# 100Hz.net
KiCad netlist of a schematic drawn in Altium Designer
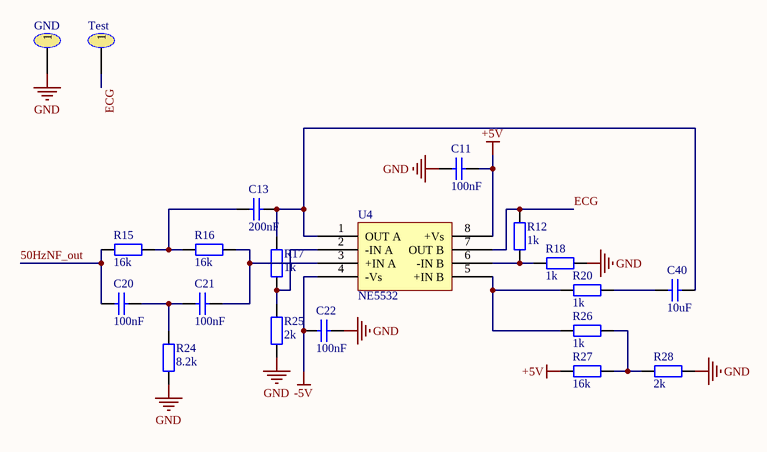
[diagram p0: 100Hz陷波&电平移位&放大.SchDoc]

(export (version "E")
  (design (tool "Eeschema 10.0.6"))
  (components
    (comp (ref "C11")
      (value "100nF")
      (footprint "LC-0805_C")
      (description "100nF��0805��50V,+/-10%")
      (libsource (lib "ECG") (part "Cap"))
    )
    (comp (ref "C13")
      (value "200nF")
      (footprint "LC-0805_C")
      (description "100nF��0805��50V,+/-10%")
      (libsource (lib "ECG") (part "Cap"))
    )
    (comp (ref "C20")
      (value "100nF")
      (footprint "LC-0805_C")
      (description "100nF��0805��50V,+/-10%")
      (libsource (lib "ECG") (part "Cap"))
    )
    (comp (ref "C21")
      (value "100nF")
      (footprint "LC-0805_C")
      (description "100nF��0805��50V,+/-10%")
      (libsource (lib "ECG") (part "Cap"))
    )
    (comp (ref "C22")
      (value "100nF")
      (footprint "LC-0805_C")
      (description "100nF��0805��50V,+/-10%")
      (libsource (lib "ECG") (part "Cap"))
    )
    (comp (ref "C40")
      (value "10uF")
      (footprint "LC-0805_C")
      (description "100nF��0805��50V,+/-10%")
      (libsource (lib "ECG") (part "Cap"))
    )
    (comp (ref "GND")
      (value "���Ժ���")
      (footprint "PAD")
      (description "��������")
      (libsource (lib "ECG") (part "TestPoint"))
    )
    (comp (ref "R12")
      (value "1k")
      (footprint "LC-0805_R")
      (description "10k��,0805,��5%")
      (libsource (lib "ECG") (part "R"))
    )
    (comp (ref "R15")
      (value "16k")
      (footprint "LC-0805_R")
      (description "10k��,0805,��5%")
      (libsource (lib "ECG") (part "R"))
    )
    (comp (ref "R16")
      (value "16k")
      (footprint "LC-0805_R")
      (description "10k��,0805,��5%")
      (libsource (lib "ECG") (part "R"))
    )
    (comp (ref "R17")
      (value "1k")
      (footprint "LC-0805_R")
      (description "10k��,0805,��5%")
      (libsource (lib "ECG") (part "R"))
    )
    (comp (ref "R18")
      (value "1k")
      (footprint "LC-0805_R")
      (description "10k��,0805,��5%")
      (libsource (lib "ECG") (part "R"))
    )
    (comp (ref "R20")
      (value "1k")
      (footprint "LC-0805_R")
      (description "10k��,0805,��5%")
      (libsource (lib "ECG") (part "R"))
    )
    (comp (ref "R24")
      (value "8.2k")
      (footprint "LC-0805_R")
      (description "10k��,0805,��5%")
      (libsource (lib "ECG") (part "R"))
    )
    (comp (ref "R25")
      (value "2k")
      (footprint "LC-0805_R")
      (description "10k��,0805,��5%")
      (libsource (lib "ECG") (part "R"))
    )
    (comp (ref "R26")
      (value "1k")
      (footprint "LC-0805_R")
      (description "10k��,0805,��5%")
      (libsource (lib "ECG") (part "R"))
    )
    (comp (ref "R27")
      (value "16k")
      (footprint "LC-0805_R")
      (description "10k��,0805,��5%")
      (libsource (lib "ECG") (part "R"))
    )
    (comp (ref "R28")
      (value "2k")
      (footprint "LC-0805_R")
      (description "10k��,0805,��5%")
      (libsource (lib "ECG") (part "R"))
    )
    (comp (ref "Test")
      (value "���Ժ���")
      (footprint "PAD")
      (description "��������")
      (libsource (lib "ECG") (part "TestPoint"))
    )
    (comp (ref "U4")
      (value "NE5532")
      (footprint "DIP-8")
      (description "NE5532��SO-8")
      (libsource (lib "ECG") (part "NE5532"))
    )
  )
  (nets
    (net (code "1") (name "+5V") (class "Default")
      (node (ref "C11") (pin "1") (pinfunction "1_1") (pintype "passive"))
      (node (ref "R27") (pin "2") (pintype "passive"))
      (node (ref "U4") (pin "8") (pinfunction "+Vs_8") (pintype "passive"))
    )
    (net (code "2") (name "-5V") (class "Default")
      (node (ref "C22") (pin "2") (pinfunction "2_2") (pintype "passive"))
      (node (ref "U4") (pin "4") (pinfunction "-Vs_4") (pintype "passive"))
    )
    (net (code "3") (name "/50HzNF_out") (class "Default")
      (node (ref "C20") (pin "2") (pinfunction "2_2") (pintype "passive"))
      (node (ref "R15") (pin "1") (pintype "passive"))
    )
    (net (code "4") (name "/ECG") (class "Default")
      (node (ref "R12") (pin "2") (pintype "passive"))
      (node (ref "Test") (pin "1") (pinfunction "1_1") (pintype "passive"))
      (node (ref "U4") (pin "7") (pinfunction "OUT_B_7") (pintype "passive"))
    )
    (net (code "5") (name "GND") (class "Default")
      (node (ref "C11") (pin "2") (pinfunction "2_2") (pintype "passive"))
      (node (ref "C22") (pin "1") (pinfunction "1_1") (pintype "passive"))
      (node (ref "GND") (pin "1") (pinfunction "1_1") (pintype "passive"))
      (node (ref "R18") (pin "1") (pintype "passive"))
      (node (ref "R24") (pin "1") (pintype "passive"))
      (node (ref "R25") (pin "1") (pintype "passive"))
      (node (ref "R28") (pin "1") (pintype "passive"))
    )
    (net (code "6") (name "Net-(C13-Pad2)") (class "Default")
      (node (ref "C13") (pin "2") (pinfunction "2_2") (pintype "passive"))
      (node (ref "R15") (pin "2") (pintype "passive"))
      (node (ref "R16") (pin "1") (pintype "passive"))
    )
    (net (code "7") (name "Net-(C20-Pad1)") (class "Default")
      (node (ref "C20") (pin "1") (pinfunction "1_1") (pintype "passive"))
      (node (ref "C21") (pin "2") (pinfunction "2_2") (pintype "passive"))
      (node (ref "R24") (pin "2") (pintype "passive"))
    )
    (net (code "8") (name "Net-(C40-Pad1)") (class "Default")
      (node (ref "C40") (pin "1") (pinfunction "1_1") (pintype "passive"))
      (node (ref "R20") (pin "1") (pintype "passive"))
    )
    (net (code "9") (name "Net-(R26-Pad1)") (class "Default")
      (node (ref "R26") (pin "1") (pintype "passive"))
      (node (ref "R27") (pin "1") (pintype "passive"))
      (node (ref "R28") (pin "2") (pintype "passive"))
    )
    (net (code "10") (name "Net-(U4-+IN_A)") (class "Default")
      (node (ref "C21") (pin "1") (pinfunction "1_1") (pintype "passive"))
      (node (ref "R16") (pin "2") (pintype "passive"))
      (node (ref "U4") (pin "3") (pinfunction "+IN_A_3") (pintype "passive"))
    )
    (net (code "11") (name "Net-(U4-+IN_B)") (class "Default")
      (node (ref "R20") (pin "2") (pintype "passive"))
      (node (ref "R26") (pin "2") (pintype "passive"))
      (node (ref "U4") (pin "5") (pinfunction "+IN_B_5") (pintype "passive"))
    )
    (net (code "12") (name "Net-(U4--IN_A)") (class "Default")
      (node (ref "R17") (pin "1") (pintype "passive"))
      (node (ref "R25") (pin "2") (pintype "passive"))
      (node (ref "U4") (pin "2") (pinfunction "-IN_A_2") (pintype "passive"))
    )
    (net (code "13") (name "Net-(U4--IN_B)") (class "Default")
      (node (ref "R12") (pin "1") (pintype "passive"))
      (node (ref "R18") (pin "2") (pintype "passive"))
      (node (ref "U4") (pin "6") (pinfunction "-IN_B_6") (pintype "passive"))
    )
    (net (code "14") (name "Net-(U4-OUT_A)") (class "Default")
      (node (ref "C13") (pin "1") (pinfunction "1_1") (pintype "passive"))
      (node (ref "C40") (pin "2") (pinfunction "2_2") (pintype "passive"))
      (node (ref "R17") (pin "2") (pintype "passive"))
      (node (ref "U4") (pin "1") (pinfunction "OUT_A_1") (pintype "passive"))
    )
  )
)
